# Atari_2600_OD.net
KiCad netlist of a schematic drawn in EAGLE
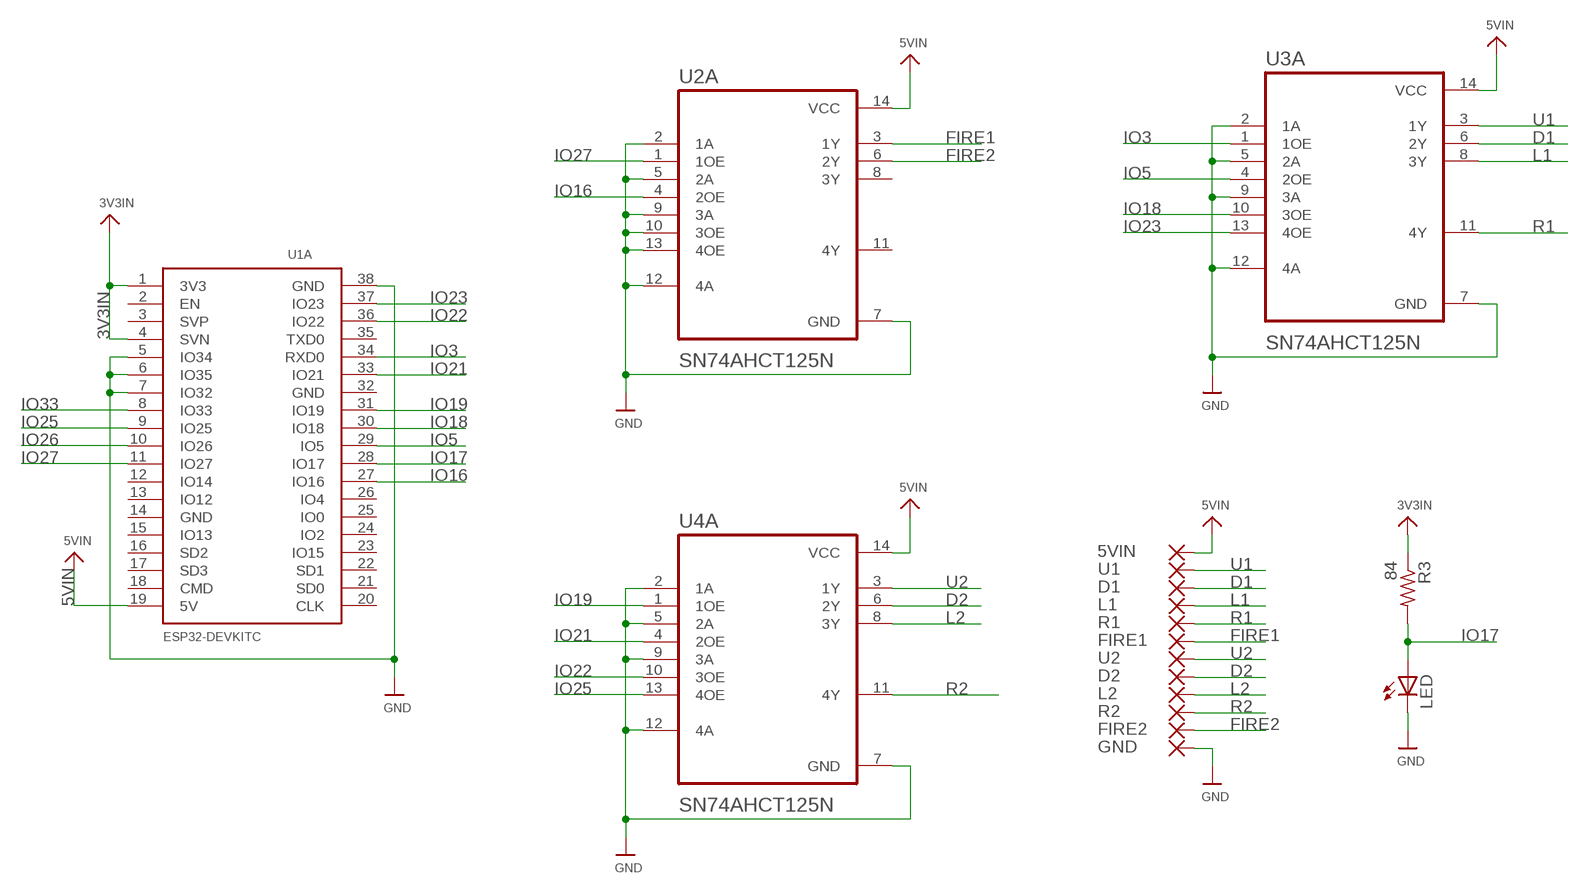
[diagram p0: schematic, sheet 1]

(export (version "E")
  (design (tool "Eeschema 10.0.6"))
  (components
    (comp (ref "5VIN")
      (value "SMD5")
      (footprint "eagle-import:SMD2,54-5,08")
      (libsource (lib "eagle-import") (part "SMD5"))
    )
    (comp (ref "D1")
      (value "SMD5")
      (footprint "eagle-import:SMD2,54-5,08")
      (libsource (lib "eagle-import") (part "SMD5"))
    )
    (comp (ref "D2")
      (value "SMD5")
      (footprint "eagle-import:SMD2,54-5,08")
      (libsource (lib "eagle-import") (part "SMD5"))
    )
    (comp (ref "FIRE1")
      (value "SMD5")
      (footprint "eagle-import:SMD2,54-5,08")
      (libsource (lib "eagle-import") (part "SMD5"))
    )
    (comp (ref "FIRE2")
      (value "SMD5")
      (footprint "eagle-import:SMD2,54-5,08")
      (libsource (lib "eagle-import") (part "SMD5"))
    )
    (comp (ref "GND")
      (value "SMD5")
      (footprint "eagle-import:SMD2,54-5,08")
      (libsource (lib "eagle-import") (part "SMD5"))
    )
    (comp (ref "L1")
      (value "SMD5")
      (footprint "eagle-import:SMD2,54-5,08")
      (libsource (lib "eagle-import") (part "SMD5"))
    )
    (comp (ref "L2")
      (value "SMD5")
      (footprint "eagle-import:SMD2,54-5,08")
      (libsource (lib "eagle-import") (part "SMD5"))
    )
    (comp (ref "LED")
      (value "LEDCHIPLED_1206")
      (footprint "eagle-import:CHIPLED_1206")
      (libsource (lib "eagle-import") (part "LEDCHIPLED_1206"))
    )
    (comp (ref "R1")
      (value "SMD5")
      (footprint "eagle-import:SMD2,54-5,08")
      (libsource (lib "eagle-import") (part "SMD5"))
    )
    (comp (ref "R2")
      (value "SMD5")
      (footprint "eagle-import:SMD2,54-5,08")
      (libsource (lib "eagle-import") (part "SMD5"))
    )
    (comp (ref "R3")
      (value "84")
      (footprint "eagle-import:R1206")
      (libsource (lib "eagle-import") (part "R-US_R1206"))
    )
    (comp (ref "U1")
      (value "SMD5")
      (footprint "eagle-import:SMD2,54-5,08")
      (libsource (lib "eagle-import") (part "SMD5"))
    )
    (comp (ref "U1A")
      (value "ESP32DEVKITC")
      (footprint "eagle-import:ESP32-DEVKITC")
      (libsource (lib "eagle-import") (part "ESP32DEVKITC"))
    )
    (comp (ref "U2")
      (value "SMD5")
      (footprint "eagle-import:SMD2,54-5,08")
      (libsource (lib "eagle-import") (part "SMD5"))
    )
    (comp (ref "U2A")
      (value "SN74AHCT125N")
      (footprint "eagle-import:DIP794W45P254L1969H508Q14")
      (fields (field (name "MF") "Texas Instruments"))
      (libsource (lib "eagle-import") (part "SN74AHCT125N"))
    )
    (comp (ref "U3A")
      (value "SN74AHCT125N")
      (footprint "eagle-import:DIP794W45P254L1969H508Q14")
      (fields (field (name "MF") "Texas Instruments"))
      (libsource (lib "eagle-import") (part "SN74AHCT125N"))
    )
    (comp (ref "U4A")
      (value "SN74AHCT125N")
      (footprint "eagle-import:DIP794W45P254L1969H508Q14")
      (fields (field (name "MF") "Texas Instruments"))
      (libsource (lib "eagle-import") (part "SN74AHCT125N"))
    )
  )
  (nets
    (net (code "1") (name "/D1") (class "Default")
      (node (ref "D1") (pin "1") (pinfunction "P_1") (pintype "passive"))
      (node (ref "U3A") (pin "6") (pinfunction "2Y_6") (pintype "output"))
    )
    (net (code "2") (name "/D2") (class "Default")
      (node (ref "D2") (pin "1") (pinfunction "P_1") (pintype "passive"))
      (node (ref "U4A") (pin "6") (pinfunction "2Y_6") (pintype "output"))
    )
    (net (code "3") (name "/FIRE1") (class "Default")
      (node (ref "FIRE1") (pin "1") (pinfunction "P_1") (pintype "passive"))
      (node (ref "U2A") (pin "3") (pinfunction "1Y_3") (pintype "output"))
    )
    (net (code "4") (name "/FIRE2") (class "Default")
      (node (ref "FIRE2") (pin "1") (pinfunction "P_1") (pintype "passive"))
      (node (ref "U2A") (pin "6") (pinfunction "2Y_6") (pintype "output"))
    )
    (net (code "5") (name "/IO3") (class "Default")
      (node (ref "U1A") (pin "34") (pinfunction "RXD0_34") (pintype "bidirectional"))
      (node (ref "U3A") (pin "1") (pinfunction "1OE_1") (pintype "input"))
    )
    (net (code "6") (name "/IO5") (class "Default")
      (node (ref "U1A") (pin "29") (pinfunction "IO5_29") (pintype "bidirectional"))
      (node (ref "U3A") (pin "4") (pinfunction "2OE_4") (pintype "input"))
    )
    (net (code "7") (name "/IO16") (class "Default")
      (node (ref "U1A") (pin "27") (pinfunction "IO16_27") (pintype "bidirectional"))
      (node (ref "U2A") (pin "4") (pinfunction "2OE_4") (pintype "input"))
    )
    (net (code "8") (name "/IO17") (class "Default")
      (node (ref "LED") (pin "A") (pinfunction "A_A") (pintype "passive"))
      (node (ref "R3") (pin "2") (pinfunction "2_2") (pintype "passive"))
      (node (ref "U1A") (pin "28") (pinfunction "IO17_28") (pintype "bidirectional"))
    )
    (net (code "9") (name "/IO18") (class "Default")
      (node (ref "U1A") (pin "30") (pinfunction "IO18_30") (pintype "bidirectional"))
      (node (ref "U3A") (pin "10") (pinfunction "3OE_10") (pintype "input"))
    )
    (net (code "10") (name "/IO19") (class "Default")
      (node (ref "U1A") (pin "31") (pinfunction "IO19_31") (pintype "bidirectional"))
      (node (ref "U4A") (pin "1") (pinfunction "1OE_1") (pintype "input"))
    )
    (net (code "11") (name "/IO21") (class "Default")
      (node (ref "U1A") (pin "33") (pinfunction "IO21_33") (pintype "bidirectional"))
      (node (ref "U4A") (pin "4") (pinfunction "2OE_4") (pintype "input"))
    )
    (net (code "12") (name "/IO22") (class "Default")
      (node (ref "U1A") (pin "36") (pinfunction "IO22_36") (pintype "bidirectional"))
      (node (ref "U4A") (pin "10") (pinfunction "3OE_10") (pintype "input"))
    )
    (net (code "13") (name "/IO23") (class "Default")
      (node (ref "U1A") (pin "37") (pinfunction "IO23_37") (pintype "bidirectional"))
      (node (ref "U3A") (pin "13") (pinfunction "4OE_13") (pintype "input"))
    )
    (net (code "14") (name "/IO25") (class "Default")
      (node (ref "U1A") (pin "9") (pinfunction "IO25_9") (pintype "bidirectional"))
      (node (ref "U4A") (pin "13") (pinfunction "4OE_13") (pintype "input"))
    )
    (net (code "15") (name "/IO26") (class "Default")
      (node (ref "U1A") (pin "10") (pinfunction "IO26_10") (pintype "bidirectional"))
    )
    (net (code "16") (name "/IO27") (class "Default")
      (node (ref "U1A") (pin "11") (pinfunction "IO27_11") (pintype "bidirectional"))
      (node (ref "U2A") (pin "1") (pinfunction "1OE_1") (pintype "input"))
    )
    (net (code "17") (name "/IO33") (class "Default")
      (node (ref "U1A") (pin "8") (pinfunction "IO33_8") (pintype "bidirectional"))
    )
    (net (code "18") (name "/L1") (class "Default")
      (node (ref "L1") (pin "1") (pinfunction "P_1") (pintype "passive"))
      (node (ref "U3A") (pin "8") (pinfunction "3Y_8") (pintype "output"))
    )
    (net (code "19") (name "/L2") (class "Default")
      (node (ref "L2") (pin "1") (pinfunction "P_1") (pintype "passive"))
      (node (ref "U4A") (pin "8") (pinfunction "3Y_8") (pintype "output"))
    )
    (net (code "20") (name "/R1") (class "Default")
      (node (ref "R1") (pin "1") (pinfunction "P_1") (pintype "passive"))
      (node (ref "U3A") (pin "11") (pinfunction "4Y_11") (pintype "output"))
    )
    (net (code "21") (name "/R2") (class "Default")
      (node (ref "R2") (pin "1") (pinfunction "P_1") (pintype "passive"))
      (node (ref "U4A") (pin "11") (pinfunction "4Y_11") (pintype "output"))
    )
    (net (code "22") (name "/U1") (class "Default")
      (node (ref "U1") (pin "1") (pinfunction "P_1") (pintype "passive"))
      (node (ref "U3A") (pin "3") (pinfunction "1Y_3") (pintype "output"))
    )
    (net (code "23") (name "/U2") (class "Default")
      (node (ref "U2") (pin "1") (pinfunction "P_1") (pintype "passive"))
      (node (ref "U4A") (pin "3") (pinfunction "1Y_3") (pintype "output"))
    )
    (net (code "24") (name "3V3IN") (class "Default")
      (node (ref "R3") (pin "1") (pinfunction "1_1") (pintype "passive"))
      (node (ref "U1A") (pin "1") (pinfunction "3V3_1") (pintype "bidirectional"))
      (node (ref "U1A") (pin "4") (pinfunction "SVN_4") (pintype "bidirectional"))
    )
    (net (code "25") (name "5VIN") (class "Default")
      (node (ref "5VIN") (pin "1") (pinfunction "P_1") (pintype "passive"))
      (node (ref "U1A") (pin "19") (pinfunction "5V_19") (pintype "bidirectional"))
      (node (ref "U2A") (pin "14") (pinfunction "VCC_14") (pintype "power_in"))
      (node (ref "U3A") (pin "14") (pinfunction "VCC_14") (pintype "power_in"))
      (node (ref "U4A") (pin "14") (pinfunction "VCC_14") (pintype "power_in"))
    )
    (net (code "26") (name "GND") (class "Default")
      (node (ref "GND") (pin "1") (pinfunction "P_1") (pintype "passive"))
      (node (ref "LED") (pin "C") (pinfunction "C_C") (pintype "passive"))
      (node (ref "U1A") (pin "38") (pinfunction "GND_38") (pintype "bidirectional"))
      (node (ref "U1A") (pin "5") (pinfunction "IO34_5") (pintype "bidirectional"))
      (node (ref "U1A") (pin "6") (pinfunction "IO35_6") (pintype "bidirectional"))
      (node (ref "U1A") (pin "7") (pinfunction "IO32_7") (pintype "bidirectional"))
      (node (ref "U2A") (pin "10") (pinfunction "3OE_10") (pintype "input"))
      (node (ref "U2A") (pin "12") (pinfunction "4A_12") (pintype "bidirectional"))
      (node (ref "U2A") (pin "13") (pinfunction "4OE_13") (pintype "input"))
      (node (ref "U2A") (pin "2") (pinfunction "1A_2") (pintype "input"))
      (node (ref "U2A") (pin "5") (pinfunction "2A_5") (pintype "input"))
      (node (ref "U2A") (pin "7") (pinfunction "GND_7") (pintype "power_in"))
      (node (ref "U2A") (pin "9") (pinfunction "3A_9") (pintype "input"))
      (node (ref "U3A") (pin "12") (pinfunction "4A_12") (pintype "bidirectional"))
      (node (ref "U3A") (pin "2") (pinfunction "1A_2") (pintype "input"))
      (node (ref "U3A") (pin "5") (pinfunction "2A_5") (pintype "input"))
      (node (ref "U3A") (pin "7") (pinfunction "GND_7") (pintype "power_in"))
      (node (ref "U3A") (pin "9") (pinfunction "3A_9") (pintype "input"))
      (node (ref "U4A") (pin "12") (pinfunction "4A_12") (pintype "bidirectional"))
      (node (ref "U4A") (pin "2") (pinfunction "1A_2") (pintype "input"))
      (node (ref "U4A") (pin "5") (pinfunction "2A_5") (pintype "input"))
      (node (ref "U4A") (pin "7") (pinfunction "GND_7") (pintype "power_in"))
      (node (ref "U4A") (pin "9") (pinfunction "3A_9") (pintype "input"))
    )
    (net (code "27") (name "unconnected-(U1A-CLK-Pad20)") (class "Default")
      (node (ref "U1A") (pin "20") (pinfunction "CLK_20") (pintype "bidirectional"))
    )
    (net (code "28") (name "unconnected-(U1A-CMD-Pad18)") (class "Default")
      (node (ref "U1A") (pin "18") (pinfunction "CMD_18") (pintype "bidirectional"))
    )
    (net (code "29") (name "unconnected-(U1A-EN-Pad2)") (class "Default")
      (node (ref "U1A") (pin "2") (pinfunction "EN_2") (pintype "bidirectional"))
    )
    (net (code "30") (name "unconnected-(U1A-GND-Pad14)") (class "Default")
      (node (ref "U1A") (pin "14") (pinfunction "GND_14") (pintype "bidirectional"))
    )
    (net (code "31") (name "unconnected-(U1A-GND-Pad32)") (class "Default")
      (node (ref "U1A") (pin "32") (pinfunction "GND_32") (pintype "bidirectional"))
    )
    (net (code "32") (name "unconnected-(U1A-IO0-Pad25)") (class "Default")
      (node (ref "U1A") (pin "25") (pinfunction "IO0_25") (pintype "bidirectional"))
    )
    (net (code "33") (name "unconnected-(U1A-IO2-Pad24)") (class "Default")
      (node (ref "U1A") (pin "24") (pinfunction "IO2_24") (pintype "bidirectional"))
    )
    (net (code "34") (name "unconnected-(U1A-IO4-Pad26)") (class "Default")
      (node (ref "U1A") (pin "26") (pinfunction "IO4_26") (pintype "bidirectional"))
    )
    (net (code "35") (name "unconnected-(U1A-IO12-Pad13)") (class "Default")
      (node (ref "U1A") (pin "13") (pinfunction "IO12_13") (pintype "bidirectional"))
    )
    (net (code "36") (name "unconnected-(U1A-IO13-Pad15)") (class "Default")
      (node (ref "U1A") (pin "15") (pinfunction "IO13_15") (pintype "bidirectional"))
    )
    (net (code "37") (name "unconnected-(U1A-IO14-Pad12)") (class "Default")
      (node (ref "U1A") (pin "12") (pinfunction "IO14_12") (pintype "bidirectional"))
    )
    (net (code "38") (name "unconnected-(U1A-IO15-Pad23)") (class "Default")
      (node (ref "U1A") (pin "23") (pinfunction "IO15_23") (pintype "bidirectional"))
    )
    (net (code "39") (name "unconnected-(U1A-SD0-Pad21)") (class "Default")
      (node (ref "U1A") (pin "21") (pinfunction "SD0_21") (pintype "bidirectional"))
    )
    (net (code "40") (name "unconnected-(U1A-SD1-Pad22)") (class "Default")
      (node (ref "U1A") (pin "22") (pinfunction "SD1_22") (pintype "bidirectional"))
    )
    (net (code "41") (name "unconnected-(U1A-SD2-Pad16)") (class "Default")
      (node (ref "U1A") (pin "16") (pinfunction "SD2_16") (pintype "bidirectional"))
    )
    (net (code "42") (name "unconnected-(U1A-SD3-Pad17)") (class "Default")
      (node (ref "U1A") (pin "17") (pinfunction "SD3_17") (pintype "bidirectional"))
    )
    (net (code "43") (name "unconnected-(U1A-SVP-Pad3)") (class "Default")
      (node (ref "U1A") (pin "3") (pinfunction "SVP_3") (pintype "bidirectional"))
    )
    (net (code "44") (name "unconnected-(U1A-TXD0-Pad35)") (class "Default")
      (node (ref "U1A") (pin "35") (pinfunction "TXD0_35") (pintype "bidirectional"))
    )
    (net (code "45") (name "unconnected-(U2A-3Y-Pad8)") (class "Default")
      (node (ref "U2A") (pin "8") (pinfunction "3Y_8") (pintype "output"))
    )
    (net (code "46") (name "unconnected-(U2A-4Y-Pad11)") (class "Default")
      (node (ref "U2A") (pin "11") (pinfunction "4Y_11") (pintype "output"))
    )
  )
)
